# aecho.net
KiCad netlist of a schematic drawn in EAGLE
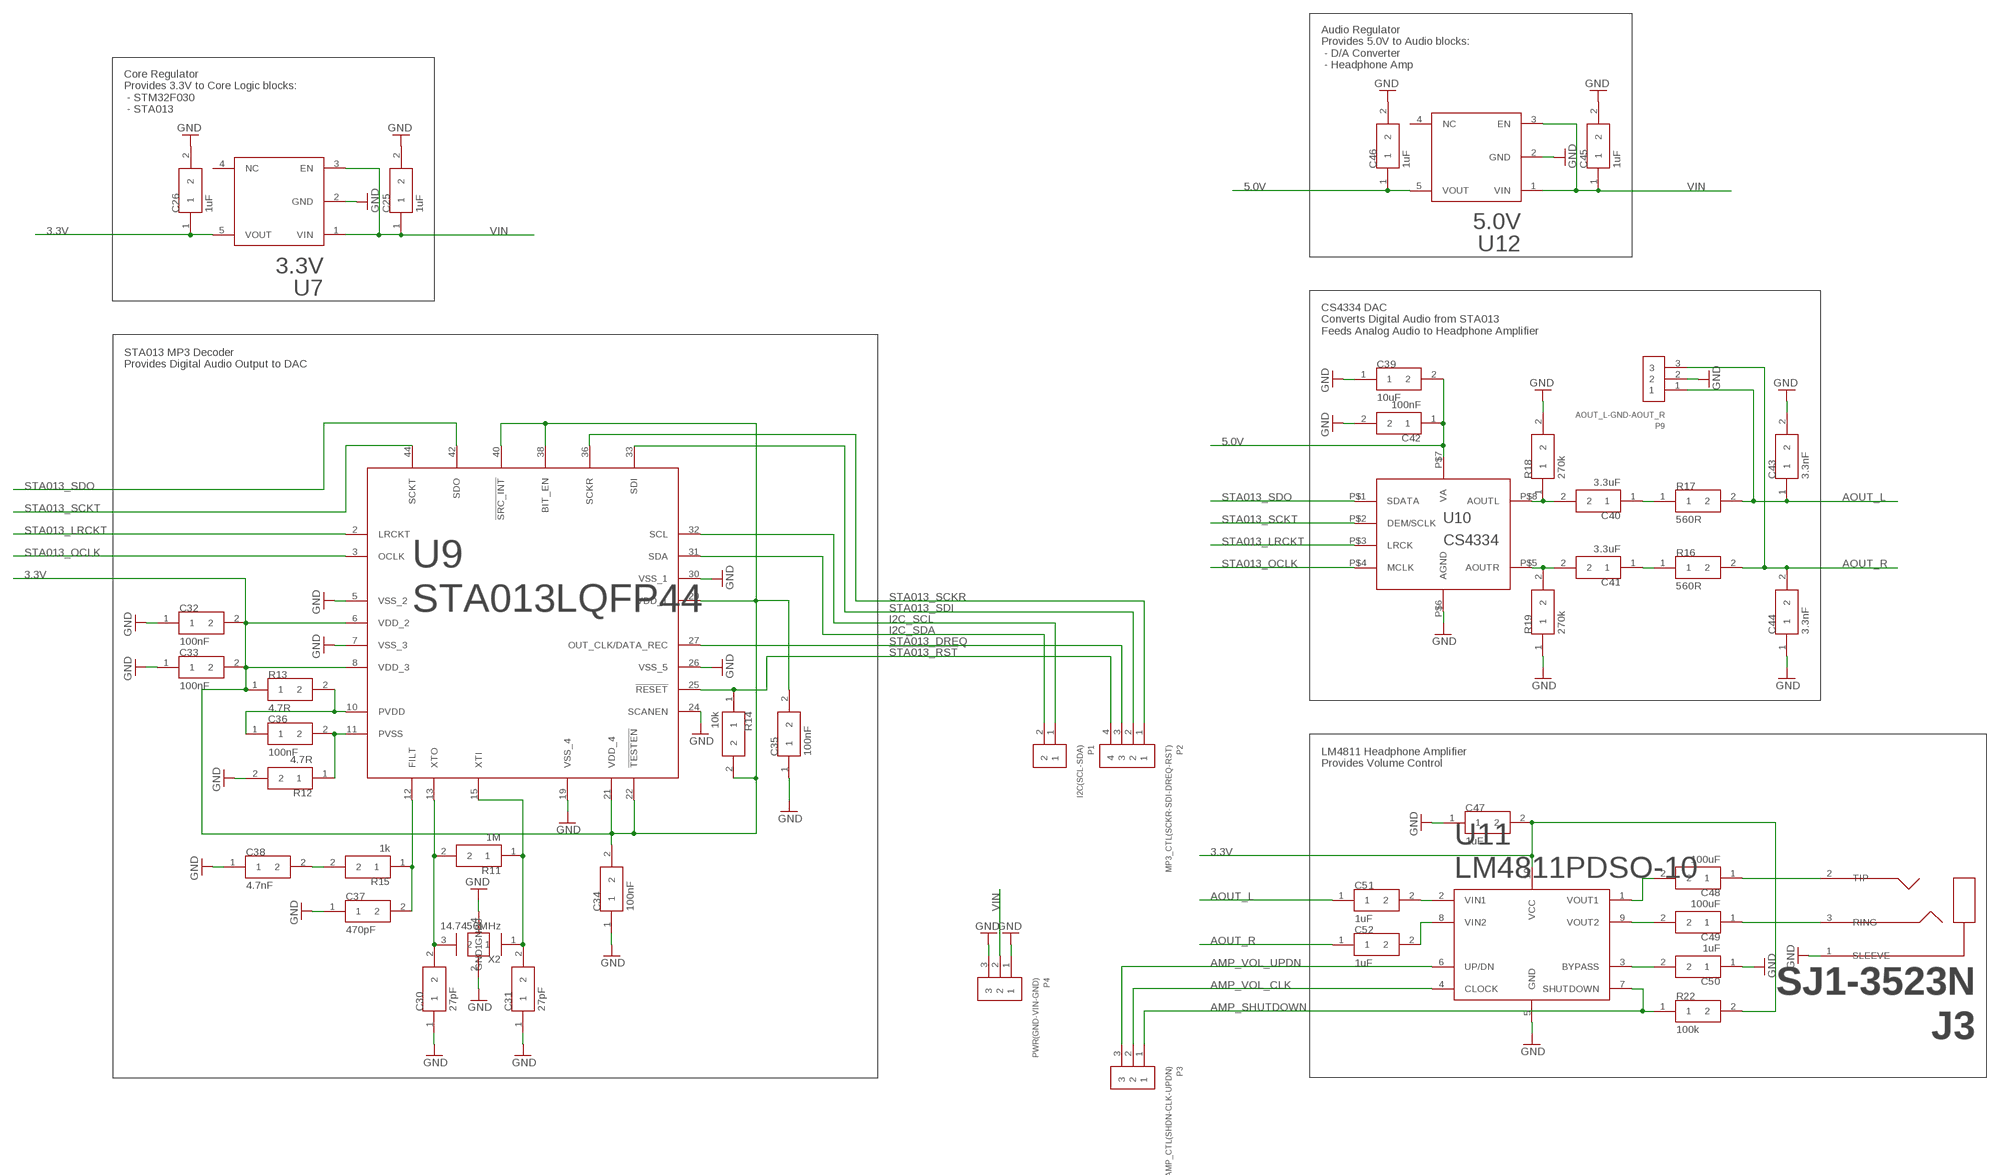
[diagram p0: schematic, sheet 1]

(export (version "E")
  (design (tool "Eeschema 10.0.6"))
  (components
    (comp (ref "C25")
      (value "1uF")
      (footprint "eagle-import:0805")
      (libsource (lib "eagle-import") (part "CAP0805"))
    )
    (comp (ref "C26")
      (value "1uF")
      (footprint "eagle-import:0805")
      (libsource (lib "eagle-import") (part "CAP0805"))
    )
    (comp (ref "C30")
      (value "27pF")
      (footprint "eagle-import:0805")
      (libsource (lib "eagle-import") (part "CAP0805"))
    )
    (comp (ref "C31")
      (value "27pF")
      (footprint "eagle-import:0805")
      (libsource (lib "eagle-import") (part "CAP0805"))
    )
    (comp (ref "C32")
      (value "100nF")
      (footprint "eagle-import:0805")
      (libsource (lib "eagle-import") (part "CAP0805"))
    )
    (comp (ref "C33")
      (value "100nF")
      (footprint "eagle-import:0805")
      (libsource (lib "eagle-import") (part "CAP0805"))
    )
    (comp (ref "C34")
      (value "100nF")
      (footprint "eagle-import:0805")
      (libsource (lib "eagle-import") (part "CAP0805"))
    )
    (comp (ref "C35")
      (value "100nF")
      (footprint "eagle-import:0805")
      (libsource (lib "eagle-import") (part "CAP0805"))
    )
    (comp (ref "C36")
      (value "100nF")
      (footprint "eagle-import:0805")
      (libsource (lib "eagle-import") (part "CAP0805"))
    )
    (comp (ref "C37")
      (value "470pF")
      (footprint "eagle-import:0805")
      (libsource (lib "eagle-import") (part "CAP0805"))
    )
    (comp (ref "C38")
      (value "4.7nF")
      (footprint "eagle-import:0805")
      (libsource (lib "eagle-import") (part "CAP0805"))
    )
    (comp (ref "C39")
      (value "10uF")
      (footprint "eagle-import:0805")
      (libsource (lib "eagle-import") (part "CAP0805"))
    )
    (comp (ref "C40")
      (value "3.3uF")
      (footprint "eagle-import:0805")
      (libsource (lib "eagle-import") (part "CAP0805"))
    )
    (comp (ref "C41")
      (value "3.3uF")
      (footprint "eagle-import:0805")
      (libsource (lib "eagle-import") (part "CAP0805"))
    )
    (comp (ref "C42")
      (value "100nF")
      (footprint "eagle-import:0805")
      (libsource (lib "eagle-import") (part "CAP0805"))
    )
    (comp (ref "C43")
      (value "3.3nF")
      (footprint "eagle-import:0805")
      (libsource (lib "eagle-import") (part "CAP0805"))
    )
    (comp (ref "C44")
      (value "3.3nF")
      (footprint "eagle-import:0805")
      (libsource (lib "eagle-import") (part "CAP0805"))
    )
    (comp (ref "C45")
      (value "1uF")
      (footprint "eagle-import:0805")
      (libsource (lib "eagle-import") (part "CAP0805"))
    )
    (comp (ref "C46")
      (value "1uF")
      (footprint "eagle-import:0805")
      (libsource (lib "eagle-import") (part "CAP0805"))
    )
    (comp (ref "C47")
      (value "1uF")
      (footprint "eagle-import:0805")
      (libsource (lib "eagle-import") (part "CAP0805"))
    )
    (comp (ref "C48")
      (value "100uF")
      (footprint "eagle-import:1210")
      (libsource (lib "eagle-import") (part "CAP1210"))
    )
    (comp (ref "C49")
      (value "100uF")
      (footprint "eagle-import:1210")
      (libsource (lib "eagle-import") (part "CAP1210"))
    )
    (comp (ref "C50")
      (value "1uF")
      (footprint "eagle-import:0805")
      (libsource (lib "eagle-import") (part "CAP0805"))
    )
    (comp (ref "C51")
      (value "1uF")
      (footprint "eagle-import:0805")
      (libsource (lib "eagle-import") (part "CAP0805"))
    )
    (comp (ref "C52")
      (value "1uF")
      (footprint "eagle-import:0805")
      (libsource (lib "eagle-import") (part "CAP0805"))
    )
    (comp (ref "J3")
      (value "SJ1-3523N")
      (footprint "eagle-import:SJ1-352XN")
      (libsource (lib "eagle-import") (part "SJ1-3523N"))
    )
    (comp (ref "P1")
      (value "I2C(SCL-SDA)")
      (footprint "eagle-import:PIN_2")
      (libsource (lib "eagle-import") (part "PIN_2"))
    )
    (comp (ref "P2")
      (value "MP3_CTL(SCKR-SDI-DREQ-RST)")
      (footprint "eagle-import:PIN_4")
      (libsource (lib "eagle-import") (part "PIN_4"))
    )
    (comp (ref "P3")
      (value "AMP_CTL(SHDN-CLK-UPDN)")
      (footprint "eagle-import:PIN_3")
      (libsource (lib "eagle-import") (part "PIN_3"))
    )
    (comp (ref "P4")
      (value "PWR(GND-VIN-GND)")
      (footprint "eagle-import:PIN_3")
      (libsource (lib "eagle-import") (part "PIN_3"))
    )
    (comp (ref "P9")
      (value "AOUT_L-GND-AOUT_R")
      (footprint "eagle-import:PIN_3")
      (libsource (lib "eagle-import") (part "PIN_3"))
    )
    (comp (ref "R11")
      (value "1M")
      (footprint "eagle-import:0805")
      (libsource (lib "eagle-import") (part "RES0805"))
    )
    (comp (ref "R12")
      (value "4.7R")
      (footprint "eagle-import:0805")
      (libsource (lib "eagle-import") (part "RES0805"))
    )
    (comp (ref "R13")
      (value "4.7R")
      (footprint "eagle-import:0805")
      (libsource (lib "eagle-import") (part "RES0805"))
    )
    (comp (ref "R14")
      (value "10k")
      (footprint "eagle-import:0805")
      (libsource (lib "eagle-import") (part "RES0805"))
    )
    (comp (ref "R15")
      (value "1k")
      (footprint "eagle-import:0805")
      (libsource (lib "eagle-import") (part "RES0805"))
    )
    (comp (ref "R16")
      (value "560R")
      (footprint "eagle-import:0805")
      (libsource (lib "eagle-import") (part "RES0805"))
    )
    (comp (ref "R17")
      (value "560R")
      (footprint "eagle-import:0805")
      (libsource (lib "eagle-import") (part "RES0805"))
    )
    (comp (ref "R18")
      (value "270k")
      (footprint "eagle-import:0805")
      (libsource (lib "eagle-import") (part "RES0805"))
    )
    (comp (ref "R19")
      (value "270k")
      (footprint "eagle-import:0805")
      (libsource (lib "eagle-import") (part "RES0805"))
    )
    (comp (ref "R22")
      (value "100k")
      (footprint "eagle-import:0805")
      (libsource (lib "eagle-import") (part "RES0805"))
    )
    (comp (ref "U7")
      (value "3.3V")
      (footprint "eagle-import:SOT23-5")
      (libsource (lib "eagle-import") (part "LP3985SOT23-5"))
    )
    (comp (ref "U9")
      (value "STA013LQFP44")
      (footprint "eagle-import:QFP44")
      (libsource (lib "eagle-import") (part "STA013LQFP44"))
    )
    (comp (ref "U10")
      (value "CS4334")
      (footprint "eagle-import:SO8")
      (libsource (lib "eagle-import") (part "CS4334"))
    )
    (comp (ref "U11")
      (value "LM4811PDSO-10")
      (footprint "eagle-import:PDSO-10")
      (libsource (lib "eagle-import") (part "LM4811PDSO-10"))
    )
    (comp (ref "U12")
      (value "5.0V")
      (footprint "eagle-import:SOT23-5")
      (libsource (lib "eagle-import") (part "LP3985SOT23-5"))
    )
    (comp (ref "X2")
      (value "14.7456MHz")
      (footprint "eagle-import:XTAL_3225")
      (libsource (lib "eagle-import") (part "XTAL_GNDSMD_3225"))
    )
  )
  (nets
    (net (code "1") (name "/3.3V") (class "Default")
      (node (ref "C26") (pin "1") (pinfunction "1_1") (pintype "bidirectional"))
      (node (ref "C32") (pin "2") (pinfunction "2_2") (pintype "bidirectional"))
      (node (ref "C33") (pin "2") (pinfunction "2_2") (pintype "bidirectional"))
      (node (ref "C34") (pin "2") (pinfunction "2_2") (pintype "bidirectional"))
      (node (ref "C35") (pin "2") (pinfunction "2_2") (pintype "bidirectional"))
      (node (ref "C47") (pin "2") (pinfunction "2_2") (pintype "bidirectional"))
      (node (ref "R13") (pin "1") (pinfunction "1_1") (pintype "bidirectional"))
      (node (ref "R14") (pin "2") (pinfunction "2_2") (pintype "bidirectional"))
      (node (ref "R22") (pin "2") (pinfunction "2_2") (pintype "bidirectional"))
      (node (ref "U11") (pin "10") (pinfunction "VCC_10") (pintype "bidirectional"))
      (node (ref "U7") (pin "5") (pinfunction "VOUT_5") (pintype "bidirectional"))
      (node (ref "U9") (pin "21") (pinfunction "VDD_4_21") (pintype "bidirectional"))
      (node (ref "U9") (pin "22") (pinfunction "~{TESTEN}_22") (pintype "bidirectional"))
      (node (ref "U9") (pin "29") (pinfunction "VDD_1_29") (pintype "bidirectional"))
      (node (ref "U9") (pin "38") (pinfunction "BIT_EN_38") (pintype "bidirectional"))
      (node (ref "U9") (pin "40") (pinfunction "~{SRC_INT}_40") (pintype "bidirectional"))
      (node (ref "U9") (pin "6") (pinfunction "VDD_2_6") (pintype "bidirectional"))
      (node (ref "U9") (pin "8") (pinfunction "VDD_3_8") (pintype "bidirectional"))
    )
    (net (code "2") (name "/5.0V") (class "Default")
      (node (ref "C39") (pin "2") (pinfunction "2_2") (pintype "bidirectional"))
      (node (ref "C42") (pin "1") (pinfunction "1_1") (pintype "bidirectional"))
      (node (ref "C46") (pin "1") (pinfunction "1_1") (pintype "bidirectional"))
      (node (ref "U10") (pin "P$7") (pinfunction "VA_P$7") (pintype "bidirectional"))
      (node (ref "U12") (pin "5") (pinfunction "VOUT_5") (pintype "bidirectional"))
    )
    (net (code "3") (name "/AMP_SHUTDOWN") (class "Default")
      (node (ref "P3") (pin "1") (pinfunction "1_1") (pintype "bidirectional"))
      (node (ref "R22") (pin "1") (pinfunction "1_1") (pintype "bidirectional"))
      (node (ref "U11") (pin "7") (pinfunction "SHUTDOWN_7") (pintype "bidirectional"))
    )
    (net (code "4") (name "/AMP_VOL_CLK") (class "Default")
      (node (ref "P3") (pin "2") (pinfunction "2_2") (pintype "bidirectional"))
      (node (ref "U11") (pin "4") (pinfunction "CLOCK_4") (pintype "bidirectional"))
    )
    (net (code "5") (name "/AMP_VOL_UPDN") (class "Default")
      (node (ref "P3") (pin "3") (pinfunction "3_3") (pintype "bidirectional"))
      (node (ref "U11") (pin "6") (pinfunction "UP/DN_6") (pintype "bidirectional"))
    )
    (net (code "6") (name "/AOUT_L") (class "Default")
      (node (ref "C43") (pin "1") (pinfunction "1_1") (pintype "bidirectional"))
      (node (ref "C51") (pin "1") (pinfunction "1_1") (pintype "bidirectional"))
      (node (ref "P9") (pin "1") (pinfunction "1_1") (pintype "bidirectional"))
      (node (ref "R17") (pin "2") (pinfunction "2_2") (pintype "bidirectional"))
    )
    (net (code "7") (name "/AOUT_R") (class "Default")
      (node (ref "C44") (pin "2") (pinfunction "2_2") (pintype "bidirectional"))
      (node (ref "C52") (pin "1") (pinfunction "1_1") (pintype "bidirectional"))
      (node (ref "P9") (pin "3") (pinfunction "3_3") (pintype "bidirectional"))
      (node (ref "R16") (pin "2") (pinfunction "2_2") (pintype "bidirectional"))
    )
    (net (code "8") (name "/I2C_SCL") (class "Default")
      (node (ref "P1") (pin "1") (pinfunction "1_1") (pintype "bidirectional"))
      (node (ref "U9") (pin "32") (pinfunction "SCL_32") (pintype "bidirectional"))
    )
    (net (code "9") (name "/I2C_SDA") (class "Default")
      (node (ref "P1") (pin "2") (pinfunction "2_2") (pintype "bidirectional"))
      (node (ref "U9") (pin "31") (pinfunction "SDA_31") (pintype "bidirectional"))
    )
    (net (code "10") (name "/STA013_DREQ") (class "Default")
      (node (ref "P2") (pin "3") (pinfunction "3_3") (pintype "bidirectional"))
      (node (ref "U9") (pin "27") (pinfunction "OUT_CLK/DATA_REC_27") (pintype "bidirectional"))
    )
    (net (code "11") (name "/STA013_LRCKT") (class "Default")
      (node (ref "U10") (pin "P$3") (pinfunction "LRCK_P$3") (pintype "bidirectional"))
      (node (ref "U9") (pin "2") (pinfunction "LRCKT_2") (pintype "bidirectional"))
    )
    (net (code "12") (name "/STA013_OCLK") (class "Default")
      (node (ref "U10") (pin "P$4") (pinfunction "MCLK_P$4") (pintype "bidirectional"))
      (node (ref "U9") (pin "3") (pinfunction "OCLK_3") (pintype "bidirectional"))
    )
    (net (code "13") (name "/STA013_SCKR") (class "Default")
      (node (ref "P2") (pin "1") (pinfunction "1_1") (pintype "bidirectional"))
      (node (ref "U9") (pin "36") (pinfunction "SCKR_36") (pintype "bidirectional"))
    )
    (net (code "14") (name "/STA013_SCKT") (class "Default")
      (node (ref "U10") (pin "P$2") (pinfunction "DEM/SCLK_P$2") (pintype "bidirectional"))
      (node (ref "U9") (pin "44") (pinfunction "SCKT_44") (pintype "bidirectional"))
    )
    (net (code "15") (name "/STA013_SDI") (class "Default")
      (node (ref "P2") (pin "2") (pinfunction "2_2") (pintype "bidirectional"))
      (node (ref "U9") (pin "33") (pinfunction "SDI_33") (pintype "bidirectional"))
    )
    (net (code "16") (name "/STA013_SDO") (class "Default")
      (node (ref "U10") (pin "P$1") (pinfunction "SDATA_P$1") (pintype "bidirectional"))
      (node (ref "U9") (pin "42") (pinfunction "SDO_42") (pintype "bidirectional"))
    )
    (net (code "17") (name "/VIN") (class "Default")
      (node (ref "C25") (pin "1") (pinfunction "1_1") (pintype "bidirectional"))
      (node (ref "C45") (pin "1") (pinfunction "1_1") (pintype "bidirectional"))
      (node (ref "P4") (pin "2") (pinfunction "2_2") (pintype "bidirectional"))
      (node (ref "U12") (pin "1") (pinfunction "VIN_1") (pintype "bidirectional"))
      (node (ref "U12") (pin "3") (pinfunction "EN_3") (pintype "bidirectional"))
      (node (ref "U7") (pin "1") (pinfunction "VIN_1") (pintype "bidirectional"))
      (node (ref "U7") (pin "3") (pinfunction "EN_3") (pintype "bidirectional"))
    )
    (net (code "18") (name "/~{STA013_RST}") (class "Default")
      (node (ref "P2") (pin "4") (pinfunction "4_4") (pintype "bidirectional"))
      (node (ref "R14") (pin "1") (pinfunction "1_1") (pintype "bidirectional"))
      (node (ref "U9") (pin "25") (pinfunction "~{RESET}_25") (pintype "bidirectional"))
    )
    (net (code "19") (name "GND") (class "Default")
      (node (ref "C25") (pin "2") (pinfunction "2_2") (pintype "bidirectional"))
      (node (ref "C26") (pin "2") (pinfunction "2_2") (pintype "bidirectional"))
      (node (ref "C30") (pin "1") (pinfunction "1_1") (pintype "bidirectional"))
      (node (ref "C31") (pin "1") (pinfunction "1_1") (pintype "bidirectional"))
      (node (ref "C32") (pin "1") (pinfunction "1_1") (pintype "bidirectional"))
      (node (ref "C33") (pin "1") (pinfunction "1_1") (pintype "bidirectional"))
      (node (ref "C34") (pin "1") (pinfunction "1_1") (pintype "bidirectional"))
      (node (ref "C35") (pin "1") (pinfunction "1_1") (pintype "bidirectional"))
      (node (ref "C37") (pin "1") (pinfunction "1_1") (pintype "bidirectional"))
      (node (ref "C38") (pin "1") (pinfunction "1_1") (pintype "bidirectional"))
      (node (ref "C39") (pin "1") (pinfunction "1_1") (pintype "bidirectional"))
      (node (ref "C42") (pin "2") (pinfunction "2_2") (pintype "bidirectional"))
      (node (ref "C43") (pin "2") (pinfunction "2_2") (pintype "bidirectional"))
      (node (ref "C44") (pin "1") (pinfunction "1_1") (pintype "bidirectional"))
      (node (ref "C45") (pin "2") (pinfunction "2_2") (pintype "bidirectional"))
      (node (ref "C46") (pin "2") (pinfunction "2_2") (pintype "bidirectional"))
      (node (ref "C47") (pin "1") (pinfunction "1_1") (pintype "bidirectional"))
      (node (ref "C50") (pin "1") (pinfunction "1_1") (pintype "bidirectional"))
      (node (ref "J3") (pin "1") (pinfunction "SLEEVE_1") (pintype "bidirectional"))
      (node (ref "P4") (pin "1") (pinfunction "1_1") (pintype "bidirectional"))
      (node (ref "P4") (pin "3") (pinfunction "3_3") (pintype "bidirectional"))
      (node (ref "P9") (pin "2") (pinfunction "2_2") (pintype "bidirectional"))
      (node (ref "R12") (pin "2") (pinfunction "2_2") (pintype "bidirectional"))
      (node (ref "R18") (pin "2") (pinfunction "2_2") (pintype "bidirectional"))
      (node (ref "R19") (pin "1") (pinfunction "1_1") (pintype "bidirectional"))
      (node (ref "U10") (pin "P$6") (pinfunction "AGND_P$6") (pintype "bidirectional"))
      (node (ref "U11") (pin "5") (pinfunction "GND_5") (pintype "bidirectional"))
      (node (ref "U12") (pin "2") (pinfunction "GND_2") (pintype "bidirectional"))
      (node (ref "U7") (pin "2") (pinfunction "GND_2") (pintype "bidirectional"))
      (node (ref "U9") (pin "19") (pinfunction "VSS_4_19") (pintype "bidirectional"))
      (node (ref "U9") (pin "24") (pinfunction "SCANEN_24") (pintype "bidirectional"))
      (node (ref "U9") (pin "26") (pinfunction "VSS_5_26") (pintype "bidirectional"))
      (node (ref "U9") (pin "30") (pinfunction "VSS_1_30") (pintype "bidirectional"))
      (node (ref "U9") (pin "5") (pinfunction "VSS_2_5") (pintype "bidirectional"))
      (node (ref "U9") (pin "7") (pinfunction "VSS_3_7") (pintype "bidirectional"))
      (node (ref "X2") (pin "2") (pinfunction "GND0_2") (pintype "bidirectional"))
      (node (ref "X2") (pin "4") (pinfunction "GND1_4") (pintype "bidirectional"))
    )
    (net (code "20") (name "Net-(C38-Pad2)") (class "Default")
      (node (ref "C38") (pin "2") (pinfunction "2_2") (pintype "bidirectional"))
      (node (ref "R15") (pin "2") (pinfunction "2_2") (pintype "bidirectional"))
    )
    (net (code "21") (name "Net-(C40-Pad1)") (class "Default")
      (node (ref "C40") (pin "1") (pinfunction "1_1") (pintype "bidirectional"))
      (node (ref "R17") (pin "1") (pinfunction "1_1") (pintype "bidirectional"))
    )
    (net (code "22") (name "Net-(C41-Pad1)") (class "Default")
      (node (ref "C41") (pin "1") (pinfunction "1_1") (pintype "bidirectional"))
      (node (ref "R16") (pin "1") (pinfunction "1_1") (pintype "bidirectional"))
    )
    (net (code "23") (name "Net-(J3-RING)") (class "Default")
      (node (ref "C49") (pin "1") (pinfunction "1_1") (pintype "bidirectional"))
      (node (ref "J3") (pin "3") (pinfunction "RING_3") (pintype "bidirectional"))
    )
    (net (code "24") (name "Net-(J3-TIP)") (class "Default")
      (node (ref "C48") (pin "1") (pinfunction "1_1") (pintype "bidirectional"))
      (node (ref "J3") (pin "2") (pinfunction "TIP_2") (pintype "bidirectional"))
    )
    (net (code "25") (name "Net-(U9-FILT)") (class "Default")
      (node (ref "C37") (pin "2") (pinfunction "2_2") (pintype "bidirectional"))
      (node (ref "R15") (pin "1") (pinfunction "1_1") (pintype "bidirectional"))
      (node (ref "U9") (pin "12") (pinfunction "FILT_12") (pintype "bidirectional"))
    )
    (net (code "26") (name "Net-(U9-PVDD)") (class "Default")
      (node (ref "C36") (pin "1") (pinfunction "1_1") (pintype "bidirectional"))
      (node (ref "R13") (pin "2") (pinfunction "2_2") (pintype "bidirectional"))
      (node (ref "U9") (pin "10") (pinfunction "PVDD_10") (pintype "bidirectional"))
    )
    (net (code "27") (name "Net-(U9-PVSS)") (class "Default")
      (node (ref "C36") (pin "2") (pinfunction "2_2") (pintype "bidirectional"))
      (node (ref "R12") (pin "1") (pinfunction "1_1") (pintype "bidirectional"))
      (node (ref "U9") (pin "11") (pinfunction "PVSS_11") (pintype "bidirectional"))
    )
    (net (code "28") (name "Net-(U9-XTI)") (class "Default")
      (node (ref "C31") (pin "2") (pinfunction "2_2") (pintype "bidirectional"))
      (node (ref "R11") (pin "1") (pinfunction "1_1") (pintype "bidirectional"))
      (node (ref "U9") (pin "15") (pinfunction "XTI_15") (pintype "bidirectional"))
      (node (ref "X2") (pin "1") (pinfunction "1_1") (pintype "bidirectional"))
    )
    (net (code "29") (name "Net-(U9-XTO)") (class "Default")
      (node (ref "C30") (pin "2") (pinfunction "2_2") (pintype "bidirectional"))
      (node (ref "R11") (pin "2") (pinfunction "2_2") (pintype "bidirectional"))
      (node (ref "U9") (pin "13") (pinfunction "XTO_13") (pintype "bidirectional"))
      (node (ref "X2") (pin "3") (pinfunction "2_3") (pintype "bidirectional"))
    )
    (net (code "30") (name "Net-(U10-AOUTL)") (class "Default")
      (node (ref "C40") (pin "2") (pinfunction "2_2") (pintype "bidirectional"))
      (node (ref "R18") (pin "1") (pinfunction "1_1") (pintype "bidirectional"))
      (node (ref "U10") (pin "P$8") (pinfunction "AOUTL_P$8") (pintype "bidirectional"))
    )
    (net (code "31") (name "Net-(U10-AOUTR)") (class "Default")
      (node (ref "C41") (pin "2") (pinfunction "2_2") (pintype "bidirectional"))
      (node (ref "R19") (pin "2") (pinfunction "2_2") (pintype "bidirectional"))
      (node (ref "U10") (pin "P$5") (pinfunction "AOUTR_P$5") (pintype "bidirectional"))
    )
    (net (code "32") (name "Net-(U11-BYPASS)") (class "Default")
      (node (ref "C50") (pin "2") (pinfunction "2_2") (pintype "bidirectional"))
      (node (ref "U11") (pin "3") (pinfunction "BYPASS_3") (pintype "bidirectional"))
    )
    (net (code "33") (name "Net-(U11-VIN1)") (class "Default")
      (node (ref "C51") (pin "2") (pinfunction "2_2") (pintype "bidirectional"))
      (node (ref "U11") (pin "2") (pinfunction "VIN1_2") (pintype "bidirectional"))
    )
    (net (code "34") (name "Net-(U11-VIN2)") (class "Default")
      (node (ref "C52") (pin "2") (pinfunction "2_2") (pintype "bidirectional"))
      (node (ref "U11") (pin "8") (pinfunction "VIN2_8") (pintype "bidirectional"))
    )
    (net (code "35") (name "Net-(U11-VOUT1)") (class "Default")
      (node (ref "C48") (pin "2") (pinfunction "2_2") (pintype "bidirectional"))
      (node (ref "U11") (pin "1") (pinfunction "VOUT1_1") (pintype "bidirectional"))
    )
    (net (code "36") (name "Net-(U11-VOUT2)") (class "Default")
      (node (ref "C49") (pin "2") (pinfunction "2_2") (pintype "bidirectional"))
      (node (ref "U11") (pin "9") (pinfunction "VOUT2_9") (pintype "bidirectional"))
    )
    (net (code "37") (name "unconnected-(U7-NC-Pad4)") (class "Default")
      (node (ref "U7") (pin "4") (pinfunction "NC_4") (pintype "bidirectional"))
    )
    (net (code "38") (name "unconnected-(U12-NC-Pad4)") (class "Default")
      (node (ref "U12") (pin "4") (pinfunction "NC_4") (pintype "bidirectional"))
    )
  )
)
